# Combine-CPU-POWER-RELAY-pth.net
KiCad netlist of a schematic drawn in EAGLE
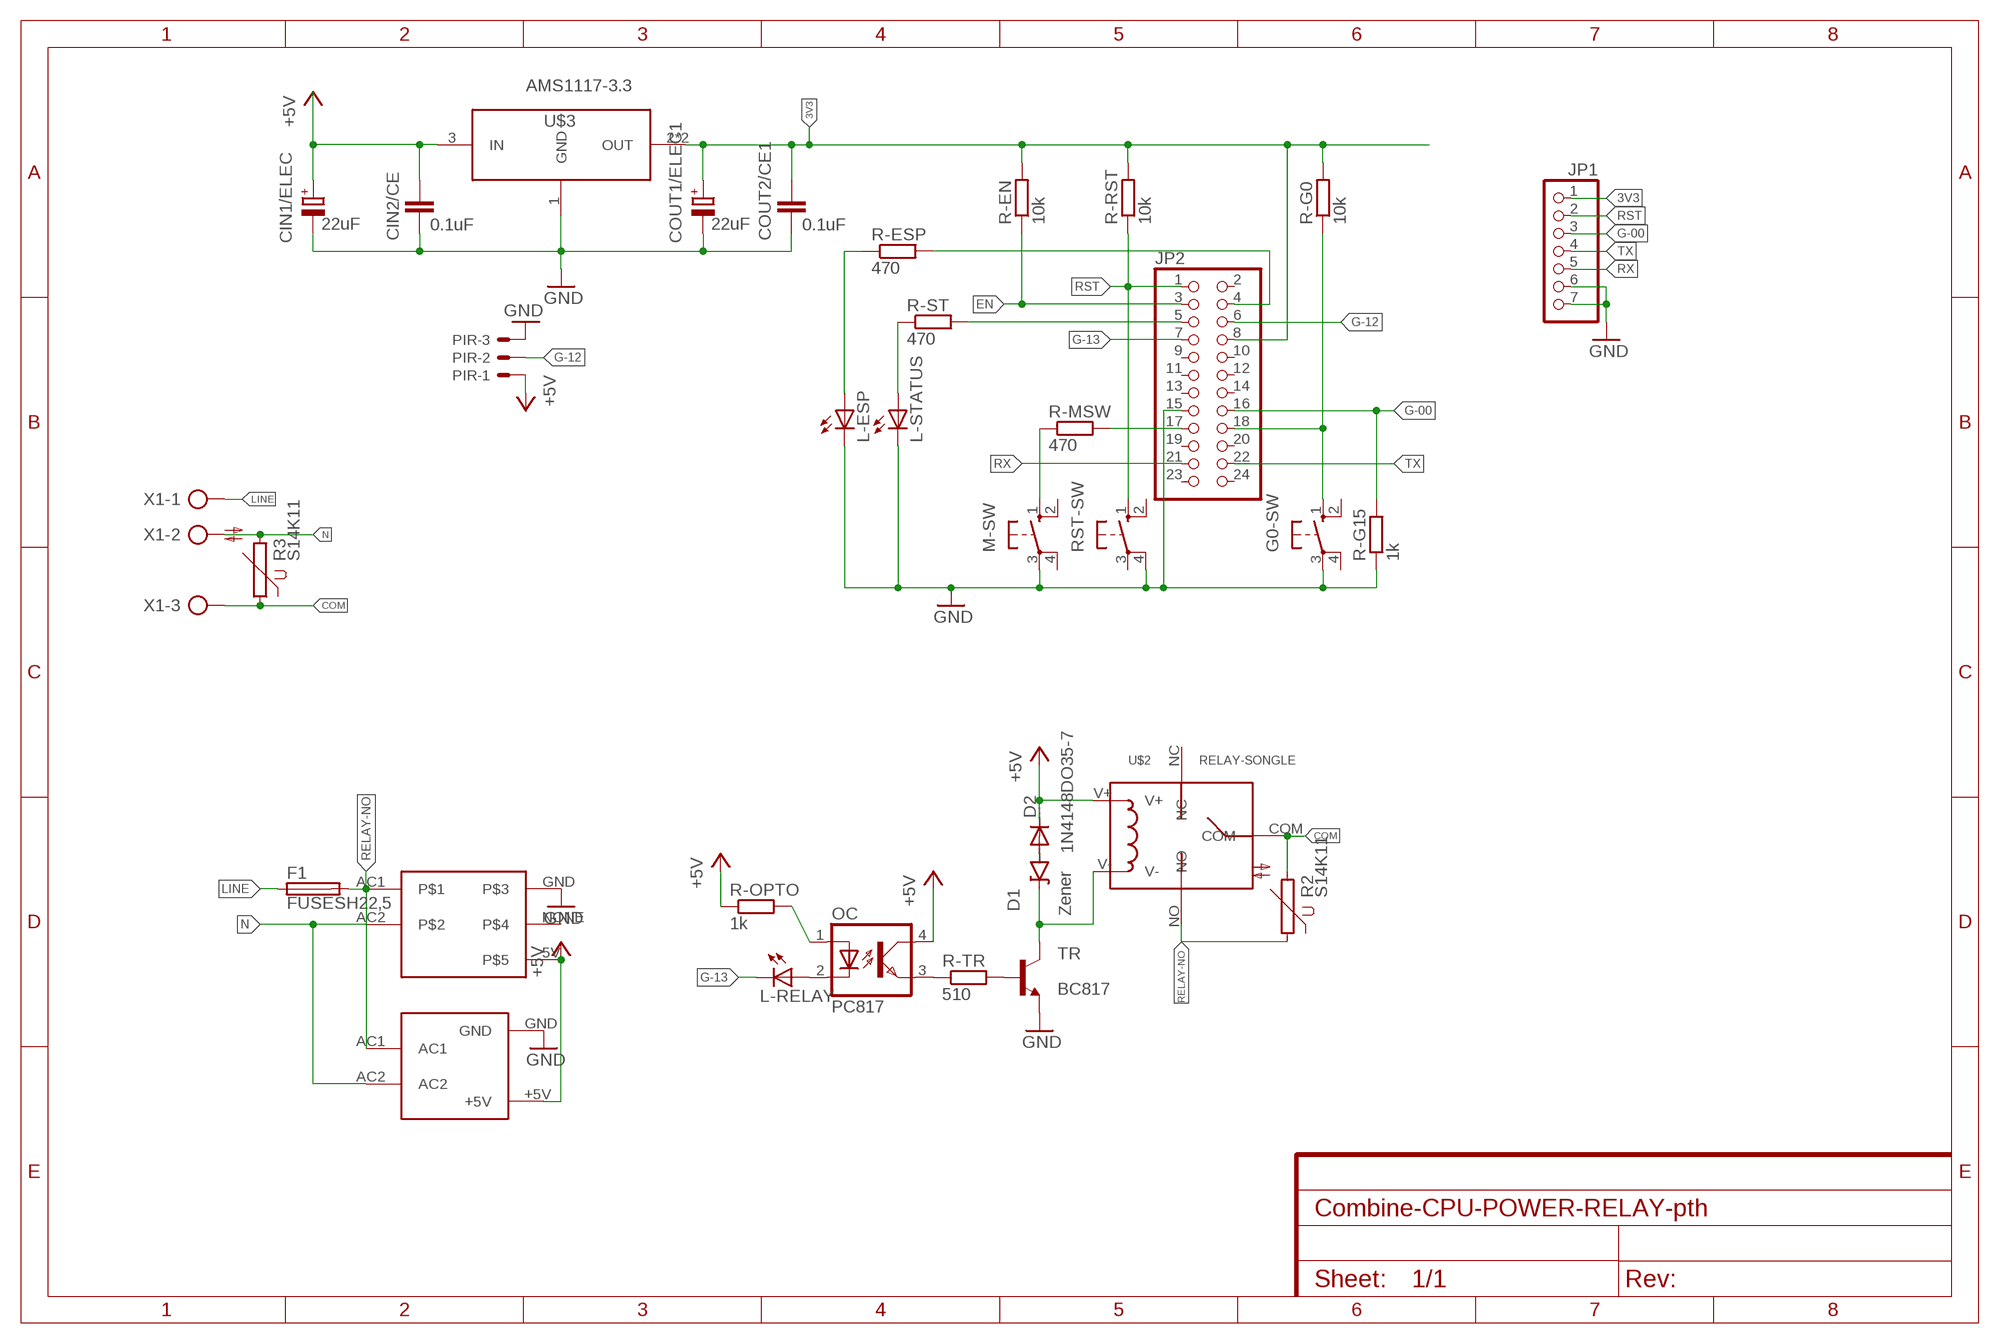
[diagram p0: schematic, sheet 1]

(export (version "E")
  (design (tool "Eeschema 10.0.6"))
  (components
    (comp (ref "CIN1/ELEC")
      (value "22uF")
      (footprint "eagle-import:E2,5-5")
      (libsource (lib "eagle-import") (part "CPOL-EUE2.5-5"))
    )
    (comp (ref "CIN2/CE")
      (value "0.1uF")
      (footprint "eagle-import:C050-024X044")
      (libsource (lib "eagle-import") (part "C-EU050-024X044"))
    )
    (comp (ref "COUT1/ELEC1")
      (value "22uF")
      (footprint "eagle-import:E2,5-5")
      (libsource (lib "eagle-import") (part "CPOL-EUE2.5-5"))
    )
    (comp (ref "COUT2/CE1")
      (value "0.1uF")
      (footprint "eagle-import:C050-024X044")
      (libsource (lib "eagle-import") (part "C-EU050-024X044"))
    )
    (comp (ref "D1")
      (value "Zener")
      (footprint "eagle-import:DIODE-ZENER")
      (libsource (lib "eagle-import") (part "DIODE-ZENERPTH"))
    )
    (comp (ref "D2")
      (value "1N4148DO35-7")
      (footprint "eagle-import:DO35-7")
      (libsource (lib "eagle-import") (part "1N4148DO35-7"))
    )
    (comp (ref "F1")
      (value "FUSESH22,5")
      (footprint "eagle-import:SH22,5")
      (libsource (lib "eagle-import") (part "FUSESH22,5"))
    )
    (comp (ref "G0-SW")
      (value "10-XX")
      (footprint "eagle-import:B3F-10XX")
      (fields (field (name "MPN") "B3F-1000"))
      (libsource (lib "eagle-import") (part "10-XX"))
    )
    (comp (ref "JP1")
      (value "PINHD-1X7")
      (footprint "eagle-import:1X07")
      (libsource (lib "eagle-import") (part "PINHD-1X7"))
    )
    (comp (ref "JP2")
      (value "PINHD-2X12")
      (footprint "eagle-import:2X12")
      (libsource (lib "eagle-import") (part "PINHD-2X12"))
    )
    (comp (ref "L-ESP")
      (value "LED3MM")
      (footprint "eagle-import:LED3MM")
      (libsource (lib "eagle-import") (part "LED3MM"))
    )
    (comp (ref "L-RELAY")
      (value "LED3MM")
      (footprint "eagle-import:LED3MM")
      (libsource (lib "eagle-import") (part "LED3MM"))
    )
    (comp (ref "L-STATUS")
      (value "LED3MM")
      (footprint "eagle-import:LED3MM")
      (libsource (lib "eagle-import") (part "LED3MM"))
    )
    (comp (ref "M-SW")
      (value "10-XX")
      (footprint "eagle-import:B3F-10XX")
      (fields (field (name "MPN") "B3F-1000"))
      (libsource (lib "eagle-import") (part "10-XX"))
    )
    (comp (ref "OC")
      (value "PC817")
      (footprint "eagle-import:DIL04")
      (fields (field (name "MPN") "PC817X4J000F"))
      (libsource (lib "eagle-import") (part "PC817"))
    )
    (comp (ref "PIR")
      (value "53048-03")
      (footprint "eagle-import:53048-03")
      (fields (field (name "MF") "WALDOM/MOLEX") (field (name "MPN") "53048-0310"))
      (libsource (lib "eagle-import") (part "53?-03048"))
    )
    (comp (ref "R-EN")
      (value "10k")
      (footprint "eagle-import:0207_2V")
      (libsource (lib "eagle-import") (part "R-EU_0207/2V"))
    )
    (comp (ref "R-ESP")
      (value "470")
      (footprint "eagle-import:0207_2V")
      (libsource (lib "eagle-import") (part "R-EU_0207/2V"))
    )
    (comp (ref "R-G0")
      (value "10k")
      (footprint "eagle-import:0207_2V")
      (libsource (lib "eagle-import") (part "R-EU_0207/2V"))
    )
    (comp (ref "R-G15")
      (value "1k")
      (footprint "eagle-import:0207_2V")
      (libsource (lib "eagle-import") (part "R-EU_0207/2V"))
    )
    (comp (ref "R-MSW")
      (value "470")
      (footprint "eagle-import:0207_2V")
      (libsource (lib "eagle-import") (part "R-EU_0207/2V"))
    )
    (comp (ref "R-OPTO")
      (value "1k")
      (footprint "eagle-import:0207_2V")
      (libsource (lib "eagle-import") (part "R-EU_0207/2V"))
    )
    (comp (ref "R-RST")
      (value "10k")
      (footprint "eagle-import:0207_2V")
      (libsource (lib "eagle-import") (part "R-EU_0207/2V"))
    )
    (comp (ref "R-ST")
      (value "470")
      (footprint "eagle-import:0207_2V")
      (libsource (lib "eagle-import") (part "R-EU_0207/2V"))
    )
    (comp (ref "R-TR")
      (value "510")
      (footprint "eagle-import:0207_2V")
      (libsource (lib "eagle-import") (part "R-EU_0207/2V"))
    )
    (comp (ref "R2")
      (value "S14K11")
      (footprint "eagle-import:S14K11")
      (libsource (lib "eagle-import") (part "S14K11"))
    )
    (comp (ref "R3")
      (value "S14K11")
      (footprint "eagle-import:S14K11")
      (libsource (lib "eagle-import") (part "S14K11"))
    )
    (comp (ref "RST-SW")
      (value "10-XX")
      (footprint "eagle-import:B3F-10XX")
      (fields (field (name "MPN") "B3F-1000"))
      (libsource (lib "eagle-import") (part "10-XX"))
    )
    (comp (ref "TR")
      (value "BC817")
      (footprint "eagle-import:SOT23-BEC")
      (libsource (lib "eagle-import") (part "BC817SMD-16"))
    )
    (comp (ref "U$1")
      (value "HLK-PM01")
      (footprint "eagle-import:HLK-PM01")
      (libsource (lib "eagle-import") (part "HLK-PM01"))
    )
    (comp (ref "U$2")
      (value "RELAY-SONGLE")
      (footprint "eagle-import:RELAY-SONGLE")
      (libsource (lib "eagle-import") (part "RELAY-SONGLE"))
    )
    (comp (ref "U$3")
      (value "AMS1117-3.3")
      (footprint "eagle-import:SOT-223")
      (libsource (lib "eagle-import") (part "AMS1117-3.3"))
    )
    (comp (ref "U$4")
      (value "POWERSUPPLY-5V-700MA")
      (footprint "eagle-import:POWERSUPPLY-5V-700MA")
      (libsource (lib "eagle-import") (part "POWERSUPPLY-5V-700MA"))
    )
    (comp (ref "X1")
      (value "AK300/3")
      (footprint "eagle-import:AK300_3")
      (libsource (lib "eagle-import") (part "AK300/3"))
    )
  )
  (nets
    (net (code "1") (name "+5V") (class "Default")
      (node (ref "CIN1/ELEC") (pin "+") (pinfunction "+_+") (pintype "passive"))
      (node (ref "CIN2/CE") (pin "1") (pinfunction "1_1") (pintype "passive"))
      (node (ref "D2") (pin "C") (pinfunction "C_C") (pintype "passive"))
      (node (ref "OC") (pin "4") (pinfunction "COL_4") (pintype "passive"))
      (node (ref "PIR") (pin "1") (pinfunction "S_1") (pintype "passive"))
      (node (ref "R-OPTO") (pin "1") (pinfunction "1_1") (pintype "passive"))
      (node (ref "U$1") (pin "+5V") (pinfunction "+5V_+5V") (pintype "bidirectional"))
      (node (ref "U$2") (pin "V+") (pinfunction "V+_V+") (pintype "bidirectional"))
      (node (ref "U$3") (pin "3") (pinfunction "IN_3") (pintype "input"))
      (node (ref "U$4") (pin "5V") (pinfunction "P$5_5V") (pintype "bidirectional"))
    )
    (net (code "2") (name "3V3") (class "Default")
      (node (ref "COUT1/ELEC1") (pin "+") (pinfunction "+_+") (pintype "passive"))
      (node (ref "COUT2/CE1") (pin "1") (pinfunction "1_1") (pintype "passive"))
      (node (ref "JP1") (pin "1") (pinfunction "1_1") (pintype "passive"))
      (node (ref "JP2") (pin "8") (pinfunction "8_8") (pintype "passive"))
      (node (ref "R-EN") (pin "2") (pinfunction "2_2") (pintype "passive"))
      (node (ref "R-G0") (pin "2") (pinfunction "2_2") (pintype "passive"))
      (node (ref "R-RST") (pin "2") (pinfunction "2_2") (pintype "passive"))
      (node (ref "U$3") (pin "2") (pinfunction "OUT_2") (pintype "output"))
      (node (ref "U$3") (pin "4") (pinfunction "OUT_4") (pintype "output"))
    )
    (net (code "3") (name "COM") (class "Default")
      (node (ref "R2") (pin "2") (pinfunction "2_2") (pintype "passive"))
      (node (ref "R3") (pin "1") (pinfunction "1_1") (pintype "passive"))
      (node (ref "U$2") (pin "COM") (pinfunction "COM_COM") (pintype "bidirectional"))
      (node (ref "X1") (pin "3") (pinfunction "KL_3") (pintype "passive"))
    )
    (net (code "4") (name "EN") (class "Default")
      (node (ref "JP2") (pin "3") (pinfunction "3_3") (pintype "passive"))
      (node (ref "R-EN") (pin "1") (pinfunction "1_1") (pintype "passive"))
    )
    (net (code "5") (name "G-00") (class "Default")
      (node (ref "JP1") (pin "3") (pinfunction "3_3") (pintype "passive"))
      (node (ref "JP2") (pin "16") (pinfunction "16_16") (pintype "passive"))
      (node (ref "R-G15") (pin "2") (pinfunction "2_2") (pintype "passive"))
    )
    (net (code "6") (name "G-12") (class "Default")
      (node (ref "JP2") (pin "6") (pinfunction "6_6") (pintype "passive"))
      (node (ref "PIR") (pin "2") (pinfunction "S_2") (pintype "passive"))
    )
    (net (code "7") (name "G-13") (class "Default")
      (node (ref "JP2") (pin "7") (pinfunction "7_7") (pintype "passive"))
      (node (ref "L-RELAY") (pin "K") (pinfunction "C_K") (pintype "passive"))
    )
    (net (code "8") (name "GND") (class "Default")
      (node (ref "CIN1/ELEC") (pin "-") (pinfunction "-_-") (pintype "passive"))
      (node (ref "CIN2/CE") (pin "2") (pinfunction "2_2") (pintype "passive"))
      (node (ref "COUT1/ELEC1") (pin "-") (pinfunction "-_-") (pintype "passive"))
      (node (ref "COUT2/CE1") (pin "2") (pinfunction "2_2") (pintype "passive"))
      (node (ref "G0-SW") (pin "3") (pinfunction "P_3") (pintype "passive"))
      (node (ref "JP1") (pin "6") (pinfunction "6_6") (pintype "passive"))
      (node (ref "JP1") (pin "7") (pinfunction "7_7") (pintype "passive"))
      (node (ref "JP2") (pin "15") (pinfunction "15_15") (pintype "passive"))
      (node (ref "L-ESP") (pin "K") (pinfunction "C_K") (pintype "passive"))
      (node (ref "L-STATUS") (pin "K") (pinfunction "C_K") (pintype "passive"))
      (node (ref "M-SW") (pin "3") (pinfunction "P_3") (pintype "passive"))
      (node (ref "PIR") (pin "3") (pinfunction "S_3") (pintype "passive"))
      (node (ref "R-G15") (pin "1") (pinfunction "1_1") (pintype "passive"))
      (node (ref "RST-SW") (pin "4") (pinfunction "P1_4") (pintype "passive"))
      (node (ref "TR") (pin "E") (pinfunction "E_E") (pintype "passive"))
      (node (ref "U$1") (pin "GND") (pinfunction "GND_GND") (pintype "bidirectional"))
      (node (ref "U$3") (pin "1") (pinfunction "GND_1") (pintype "passive"))
      (node (ref "U$4") (pin "GND") (pinfunction "P$3_GND") (pintype "bidirectional"))
    )
    (net (code "9") (name "LINE") (class "Default")
      (node (ref "F1") (pin "1") (pinfunction "1_1") (pintype "passive"))
      (node (ref "X1") (pin "1") (pinfunction "KL_1") (pintype "passive"))
    )
    (net (code "10") (name "N") (class "Default")
      (node (ref "R3") (pin "2") (pinfunction "2_2") (pintype "passive"))
      (node (ref "U$1") (pin "AC2") (pinfunction "AC2_AC2") (pintype "bidirectional"))
      (node (ref "U$4") (pin "AC2") (pinfunction "P$2_AC2") (pintype "bidirectional"))
      (node (ref "X1") (pin "2") (pinfunction "KL_2") (pintype "passive"))
    )
    (net (code "11") (name "Net-(D1-A)") (class "Default")
      (node (ref "D1") (pin "P$2") (pinfunction "A_P$2") (pintype "passive"))
      (node (ref "D2") (pin "A") (pinfunction "A_A") (pintype "passive"))
    )
    (net (code "12") (name "Net-(D1-C)") (class "Default")
      (node (ref "D1") (pin "P$1") (pinfunction "C_P$1") (pintype "passive"))
      (node (ref "TR") (pin "C") (pinfunction "C_C") (pintype "passive"))
      (node (ref "U$2") (pin "V-") (pinfunction "V-_V-") (pintype "bidirectional"))
    )
    (net (code "13") (name "Net-(G0-SW-S)") (class "Default")
      (node (ref "G0-SW") (pin "1") (pinfunction "S_1") (pintype "passive"))
      (node (ref "JP2") (pin "18") (pinfunction "18_18") (pintype "passive"))
      (node (ref "R-G0") (pin "1") (pinfunction "1_1") (pintype "passive"))
    )
    (net (code "14") (name "Net-(JP2-Pad4)") (class "Default")
      (node (ref "JP2") (pin "4") (pinfunction "4_4") (pintype "passive"))
      (node (ref "R-ESP") (pin "2") (pinfunction "2_2") (pintype "passive"))
    )
    (net (code "15") (name "Net-(JP2-Pad5)") (class "Default")
      (node (ref "JP2") (pin "5") (pinfunction "5_5") (pintype "passive"))
      (node (ref "R-ST") (pin "2") (pinfunction "2_2") (pintype "passive"))
    )
    (net (code "16") (name "Net-(JP2-Pad17)") (class "Default")
      (node (ref "JP2") (pin "17") (pinfunction "17_17") (pintype "passive"))
      (node (ref "R-MSW") (pin "2") (pinfunction "2_2") (pintype "passive"))
    )
    (net (code "17") (name "Net-(L-ESP-PadA)") (class "Default")
      (node (ref "L-ESP") (pin "A") (pinfunction "A_A") (pintype "passive"))
      (node (ref "R-ESP") (pin "1") (pinfunction "1_1") (pintype "passive"))
    )
    (net (code "18") (name "Net-(L-STATUS-PadA)") (class "Default")
      (node (ref "L-STATUS") (pin "A") (pinfunction "A_A") (pintype "passive"))
      (node (ref "R-ST") (pin "1") (pinfunction "1_1") (pintype "passive"))
    )
    (net (code "19") (name "Net-(M-SW-S)") (class "Default")
      (node (ref "M-SW") (pin "1") (pinfunction "S_1") (pintype "passive"))
      (node (ref "R-MSW") (pin "1") (pinfunction "1_1") (pintype "passive"))
    )
    (net (code "20") (name "Net-(OC-A)") (class "Default")
      (node (ref "OC") (pin "1") (pinfunction "A_1") (pintype "passive"))
      (node (ref "R-OPTO") (pin "2") (pinfunction "2_2") (pintype "passive"))
    )
    (net (code "21") (name "Net-(OC-C)") (class "Default")
      (node (ref "L-RELAY") (pin "A") (pinfunction "A_A") (pintype "passive"))
      (node (ref "OC") (pin "2") (pinfunction "C_2") (pintype "passive"))
    )
    (net (code "22") (name "Net-(OC-EMIT)") (class "Default")
      (node (ref "OC") (pin "3") (pinfunction "EMIT_3") (pintype "passive"))
      (node (ref "R-TR") (pin "1") (pinfunction "1_1") (pintype "passive"))
    )
    (net (code "23") (name "Net-(R-TR-Pad2)") (class "Default")
      (node (ref "R-TR") (pin "2") (pinfunction "2_2") (pintype "passive"))
      (node (ref "TR") (pin "B") (pinfunction "B_B") (pintype "passive"))
    )
    (net (code "24") (name "RELAY-NO") (class "Default")
      (node (ref "F1") (pin "2") (pinfunction "2_2") (pintype "passive"))
      (node (ref "R2") (pin "1") (pinfunction "1_1") (pintype "passive"))
      (node (ref "U$1") (pin "AC1") (pinfunction "AC1_AC1") (pintype "bidirectional"))
      (node (ref "U$2") (pin "NO") (pinfunction "NO_NO") (pintype "bidirectional"))
      (node (ref "U$4") (pin "AC1") (pinfunction "P$1_AC1") (pintype "bidirectional"))
    )
    (net (code "25") (name "RST") (class "Default")
      (node (ref "JP1") (pin "2") (pinfunction "2_2") (pintype "passive"))
      (node (ref "JP2") (pin "1") (pinfunction "1_1") (pintype "passive"))
      (node (ref "R-RST") (pin "1") (pinfunction "1_1") (pintype "passive"))
      (node (ref "RST-SW") (pin "1") (pinfunction "S_1") (pintype "passive"))
    )
    (net (code "26") (name "RX") (class "Default")
      (node (ref "JP1") (pin "5") (pinfunction "5_5") (pintype "passive"))
      (node (ref "JP2") (pin "21") (pinfunction "21_21") (pintype "passive"))
    )
    (net (code "27") (name "TX") (class "Default")
      (node (ref "JP1") (pin "4") (pinfunction "4_4") (pintype "passive"))
      (node (ref "JP2") (pin "22") (pinfunction "22_22") (pintype "passive"))
    )
    (net (code "28") (name "unconnected-(G0-SW-P1-Pad4)") (class "Default")
      (node (ref "G0-SW") (pin "4") (pinfunction "P1_4") (pintype "passive"))
    )
    (net (code "29") (name "unconnected-(G0-SW-S1-Pad2)") (class "Default")
      (node (ref "G0-SW") (pin "2") (pinfunction "S1_2") (pintype "passive"))
    )
    (net (code "30") (name "unconnected-(JP2-Pad2)") (class "Default")
      (node (ref "JP2") (pin "2") (pinfunction "2_2") (pintype "passive"))
    )
    (net (code "31") (name "unconnected-(JP2-Pad9)") (class "Default")
      (node (ref "JP2") (pin "9") (pinfunction "9_9") (pintype "passive"))
    )
    (net (code "32") (name "unconnected-(JP2-Pad10)") (class "Default")
      (node (ref "JP2") (pin "10") (pinfunction "10_10") (pintype "passive"))
    )
    (net (code "33") (name "unconnected-(JP2-Pad11)") (class "Default")
      (node (ref "JP2") (pin "11") (pinfunction "11_11") (pintype "passive"))
    )
    (net (code "34") (name "unconnected-(JP2-Pad12)") (class "Default")
      (node (ref "JP2") (pin "12") (pinfunction "12_12") (pintype "passive"))
    )
    (net (code "35") (name "unconnected-(JP2-Pad13)") (class "Default")
      (node (ref "JP2") (pin "13") (pinfunction "13_13") (pintype "passive"))
    )
    (net (code "36") (name "unconnected-(JP2-Pad14)") (class "Default")
      (node (ref "JP2") (pin "14") (pinfunction "14_14") (pintype "passive"))
    )
    (net (code "37") (name "unconnected-(JP2-Pad19)") (class "Default")
      (node (ref "JP2") (pin "19") (pinfunction "19_19") (pintype "passive"))
    )
    (net (code "38") (name "unconnected-(JP2-Pad20)") (class "Default")
      (node (ref "JP2") (pin "20") (pinfunction "20_20") (pintype "passive"))
    )
    (net (code "39") (name "unconnected-(JP2-Pad23)") (class "Default")
      (node (ref "JP2") (pin "23") (pinfunction "23_23") (pintype "passive"))
    )
    (net (code "40") (name "unconnected-(JP2-Pad24)") (class "Default")
      (node (ref "JP2") (pin "24") (pinfunction "24_24") (pintype "passive"))
    )
    (net (code "41") (name "unconnected-(M-SW-P1-Pad4)") (class "Default")
      (node (ref "M-SW") (pin "4") (pinfunction "P1_4") (pintype "passive"))
    )
    (net (code "42") (name "unconnected-(M-SW-S1-Pad2)") (class "Default")
      (node (ref "M-SW") (pin "2") (pinfunction "S1_2") (pintype "passive"))
    )
    (net (code "43") (name "unconnected-(RST-SW-P-Pad3)") (class "Default")
      (node (ref "RST-SW") (pin "3") (pinfunction "P_3") (pintype "passive"))
    )
    (net (code "44") (name "unconnected-(RST-SW-S1-Pad2)") (class "Default")
      (node (ref "RST-SW") (pin "2") (pinfunction "S1_2") (pintype "passive"))
    )
    (net (code "45") (name "unconnected-(U$2-PadNC)") (class "Default")
      (node (ref "U$2") (pin "NC") (pinfunction "NC_NC") (pintype "bidirectional"))
    )
    (net (code "46") (name "unconnected-(U$4-P$4-PadNONE)") (class "Default")
      (node (ref "U$4") (pin "NONE") (pinfunction "P$4_NONE") (pintype "bidirectional"))
    )
  )
)
